# MCU.net
KiCad netlist of a schematic drawn in Altium Designer
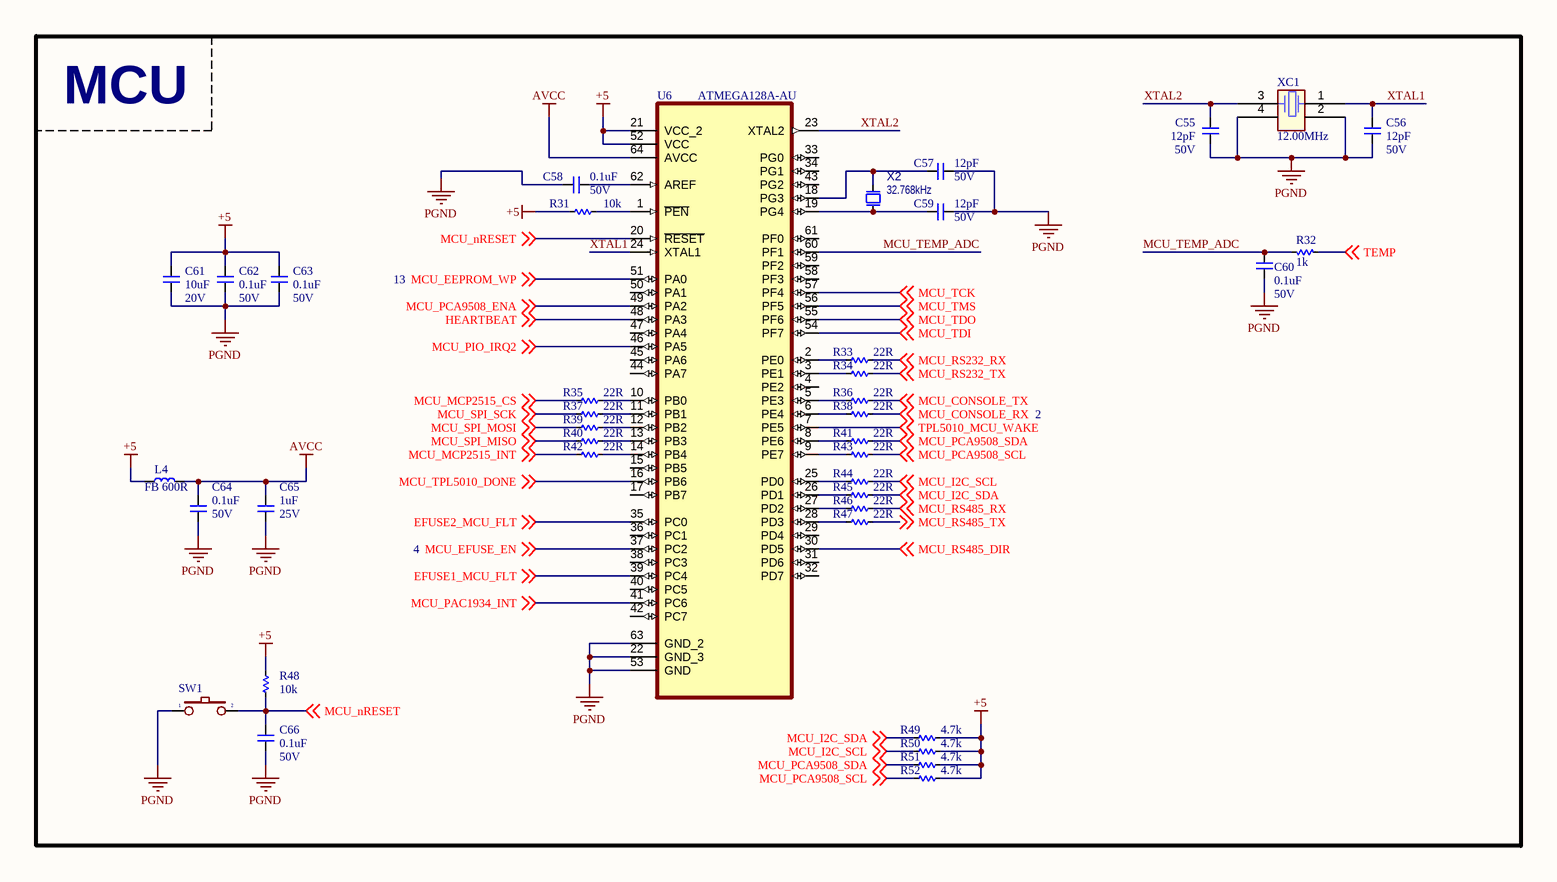
[diagram p0: MCU.SchDoc, left]
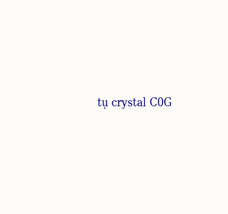
[diagram p1: MCU.SchDoc, right]

(export (version "E")
  (design (tool "Eeschema 10.0.6"))
  (components
    (comp (ref "C55")
      (value "12pF")
      (footprint "CAP_C_1608X80")
      (description "CAP")
      (fields (field (name "VOLTAGE") "50V"))
      (libsource (lib "LABLIB") (part "_CAP_C_2"))
    )
    (comp (ref "C56")
      (value "12pF")
      (footprint "CAP_C_1608X80")
      (description "CAP")
      (fields (field (name "VOLTAGE") "50V"))
      (libsource (lib "LABLIB") (part "_CAP_C_2"))
    )
    (comp (ref "C57")
      (value "12pF")
      (footprint "CAP_C_1608X80")
      (description "CAP")
      (fields (field (name "VOLTAGE") "50V"))
      (libsource (lib "LABLIB") (part "_CAP_C_2"))
    )
    (comp (ref "C58")
      (value "0.1uF")
      (footprint "CAP_C_1608X80")
      (description "CAP")
      (fields (field (name "VOLTAGE") "50V"))
      (libsource (lib "LABLIB") (part "_CAP_C_2"))
    )
    (comp (ref "C59")
      (value "12pF")
      (footprint "CAP_C_1608X80")
      (description "CAP")
      (fields (field (name "VOLTAGE") "50V"))
      (libsource (lib "LABLIB") (part "_CAP_C_2"))
    )
    (comp (ref "C60")
      (value "0.1uF")
      (footprint "CAP_C_1608X80")
      (description "CAP")
      (fields (field (name "VOLTAGE") "50V"))
      (libsource (lib "LABLIB") (part "_CAP_C_2"))
    )
    (comp (ref "C61")
      (value "10uF")
      (footprint "CAP_C_2012X110")
      (description "CAP")
      (fields (field (name "VOLTAGE") "20V"))
      (libsource (lib "LABLIB") (part "_CAP_C_2"))
    )
    (comp (ref "C62")
      (value "0.1uF")
      (footprint "CAP_C_1608X80")
      (description "CAP")
      (fields (field (name "VOLTAGE") "50V"))
      (libsource (lib "LABLIB") (part "_CAP_C_2"))
    )
    (comp (ref "C63")
      (value "0.1uF")
      (footprint "CAP_C_1608X80")
      (description "CAP")
      (fields (field (name "VOLTAGE") "50V"))
      (libsource (lib "LABLIB") (part "_CAP_C_2"))
    )
    (comp (ref "C64")
      (value "0.1uF")
      (footprint "CAP_C_1608X80")
      (description "CAP")
      (fields (field (name "VOLTAGE") "50V"))
      (libsource (lib "LABLIB") (part "_CAP_C_2"))
    )
    (comp (ref "C65")
      (value "1uF")
      (footprint "CAP_C_1608X80")
      (description "CAP")
      (fields (field (name "VOLTAGE") "25V"))
      (libsource (lib "LABLIB") (part "_CAP_C_2"))
    )
    (comp (ref "C66")
      (value "0.1uF")
      (footprint "CAP_C_1608X80")
      (description "CAP")
      (fields (field (name "VOLTAGE") "50V"))
      (libsource (lib "LABLIB") (part "_CAP_C_2"))
    )
    (comp (ref "L4")
      (value "FB 600R")
      (footprint "L-SMD-0603")
      (description "Ferrite Bread")
      (libsource (lib "chipfc_libs") (part "Inductor"))
    )
    (comp (ref "R31")
      (value "10k")
      (footprint "RES_C_1608X60")
      (description "RES")
      (libsource (lib "LABLIB") (part "_RES_B_2_2"))
    )
    (comp (ref "R32")
      (value "1k")
      (footprint "RES_C_1608X60")
      (description "RES")
      (libsource (lib "LABLIB") (part "_RES_B_2_2"))
    )
    (comp (ref "R33")
      (value "22R")
      (footprint "RES_C_1608X60")
      (description "RES")
      (libsource (lib "LABLIB") (part "_RES_B_2_2"))
    )
    (comp (ref "R34")
      (value "22R")
      (footprint "RES_C_1608X60")
      (description "RES")
      (libsource (lib "LABLIB") (part "_RES_B_2_2"))
    )
    (comp (ref "R35")
      (value "22R")
      (footprint "RES_C_1608X60")
      (description "RES")
      (libsource (lib "LABLIB") (part "_RES_B_2_2"))
    )
    (comp (ref "R36")
      (value "22R")
      (footprint "RES_C_1608X60")
      (description "RES")
      (libsource (lib "LABLIB") (part "_RES_B_2_2"))
    )
    (comp (ref "R37")
      (value "22R")
      (footprint "RES_C_1608X60")
      (description "RES")
      (libsource (lib "LABLIB") (part "_RES_B_2_2"))
    )
    (comp (ref "R38")
      (value "22R")
      (footprint "RES_C_1608X60")
      (description "RES")
      (libsource (lib "LABLIB") (part "_RES_B_2_2"))
    )
    (comp (ref "R39")
      (value "22R")
      (footprint "RES_C_1608X60")
      (description "RES")
      (libsource (lib "LABLIB") (part "_RES_B_2_2"))
    )
    (comp (ref "R40")
      (value "22R")
      (footprint "RES_C_1608X60")
      (description "RES")
      (libsource (lib "LABLIB") (part "_RES_B_2_2"))
    )
    (comp (ref "R41")
      (value "22R")
      (footprint "RES_C_1608X60")
      (description "RES")
      (libsource (lib "LABLIB") (part "_RES_B_2_2"))
    )
    (comp (ref "R42")
      (value "22R")
      (footprint "RES_C_1608X60")
      (description "RES")
      (libsource (lib "LABLIB") (part "_RES_B_2_2"))
    )
    (comp (ref "R43")
      (value "22R")
      (footprint "RES_C_1608X60")
      (description "RES")
      (libsource (lib "LABLIB") (part "_RES_B_2_2"))
    )
    (comp (ref "R44")
      (value "22R")
      (footprint "RES_C_1608X60")
      (description "RES")
      (libsource (lib "LABLIB") (part "_RES_B_2_2"))
    )
    (comp (ref "R45")
      (value "22R")
      (footprint "RES_C_1608X60")
      (description "RES")
      (libsource (lib "LABLIB") (part "_RES_B_2_2"))
    )
    (comp (ref "R46")
      (value "22R")
      (footprint "RES_C_1608X60")
      (description "RES")
      (libsource (lib "LABLIB") (part "_RES_B_2_2"))
    )
    (comp (ref "R47")
      (value "22R")
      (footprint "RES_C_1608X60")
      (description "RES")
      (libsource (lib "LABLIB") (part "_RES_B_2_2"))
    )
    (comp (ref "R48")
      (value "10k")
      (footprint "RES_C_1608X60")
      (description "RES")
      (libsource (lib "LABLIB") (part "_RES_B_2_2"))
    )
    (comp (ref "R49")
      (value "4.7k")
      (footprint "RES_C_1608X60")
      (description "RES")
      (libsource (lib "LABLIB") (part "_RES_B_2_2"))
    )
    (comp (ref "R50")
      (value "4.7k")
      (footprint "RES_C_1608X60")
      (description "RES")
      (libsource (lib "LABLIB") (part "_RES_B_2_2"))
    )
    (comp (ref "R51")
      (value "4.7k")
      (footprint "RES_C_1608X60")
      (description "RES")
      (libsource (lib "LABLIB") (part "_RES_B_2_2"))
    )
    (comp (ref "R52")
      (value "4.7k")
      (footprint "RES_C_1608X60")
      (description "RES")
      (libsource (lib "LABLIB") (part "_RES_B_2_2"))
    )
    (comp (ref "SW1")
      (value "SW2")
      (footprint "SW1-SMD")
      (description "Switch button 2 pin")
      (libsource (lib "LABLIB") (part "SW2"))
    )
    (comp (ref "U6")
      (value "ATMEGA128A-AU")
      (footprint "TQFP-64")
      (libsource (lib "KIENASIY123_LIB") (part "ATMEGA128A-AU"))
    )
    (comp (ref "X2")
      (value "32.768kHz")
      (footprint "CRYSTAL_NX2012SA")
      (description "Crystal")
      (fields
        (field (name "TOLERANCE") "±20ppm")
        (field (name "Comment") "Crystal 2 Pins")
        (field (name "OWNER") "Jamus Griego")
      )
      (libsource (lib "LABLIB") (part "OSC_32.768kHz"))
    )
    (comp (ref "XC1")
      (value "12.00MHz")
      (footprint "AP7-00039")
      (description "Fox FQ5032B 12.0MHz SMD crystal 738B-12")
      (fields (field (name "TOLERANCE") "Â±30ppm") (field (name "MANUFACTURER") "Fox  Electronics"))
      (libsource (lib "AltiumDbLib") (part "CRYSTAL1324"))
    )
  )
  (nets
    (net (code "1") (name "+5") (class "Default")
      (node (ref "C61") (pin "2") (pinfunction "2_2") (pintype "passive"))
      (node (ref "C62") (pin "1") (pinfunction "1_1") (pintype "passive"))
      (node (ref "C63") (pin "1") (pinfunction "1_1") (pintype "passive"))
      (node (ref "L4") (pin "1") (pinfunction "1_1") (pintype "passive"))
      (node (ref "R31") (pin "1") (pinfunction "1_1") (pintype "passive"))
      (node (ref "R48") (pin "1") (pinfunction "1_1") (pintype "passive"))
      (node (ref "R49") (pin "1") (pinfunction "1_1") (pintype "passive"))
      (node (ref "R50") (pin "1") (pinfunction "1_1") (pintype "passive"))
      (node (ref "R51") (pin "1") (pinfunction "1_1") (pintype "passive"))
      (node (ref "R52") (pin "1") (pinfunction "1_1") (pintype "passive"))
      (node (ref "U6") (pin "21") (pinfunction "VCC_2_21") (pintype "power_in"))
      (node (ref "U6") (pin "52") (pinfunction "VCC_52") (pintype "power_in"))
    )
    (net (code "2") (name "/MCU_TEMP_ADC") (class "Default")
      (node (ref "C60") (pin "1") (pinfunction "1_1") (pintype "passive"))
      (node (ref "R32") (pin "2") (pinfunction "2_2") (pintype "passive"))
      (node (ref "U6") (pin "60") (pinfunction "PF1_60") (pintype "bidirectional"))
    )
    (net (code "3") (name "/XTAL1") (class "Default")
      (node (ref "C56") (pin "2") (pinfunction "2_2") (pintype "passive"))
      (node (ref "U6") (pin "24") (pinfunction "XTAL1_24") (pintype "input"))
      (node (ref "XC1") (pin "1") (pinfunction "1_1") (pintype "passive"))
    )
    (net (code "4") (name "/XTAL2") (class "Default")
      (node (ref "C55") (pin "2") (pinfunction "2_2") (pintype "passive"))
      (node (ref "U6") (pin "23") (pinfunction "XTAL2_23") (pintype "output"))
      (node (ref "XC1") (pin "3") (pinfunction "3_3") (pintype "passive"))
    )
    (net (code "5") (name "AVCC") (class "Default")
      (node (ref "C64") (pin "1") (pinfunction "1_1") (pintype "passive"))
      (node (ref "C65") (pin "1") (pinfunction "1_1") (pintype "passive"))
      (node (ref "L4") (pin "2") (pinfunction "2_2") (pintype "passive"))
      (node (ref "U6") (pin "64") (pinfunction "AVCC_64") (pintype "power_in"))
    )
    (net (code "6") (name "EFUSE1_MCU_FLT") (class "Default")
      (node (ref "U6") (pin "39") (pinfunction "PC4_39") (pintype "bidirectional"))
    )
    (net (code "7") (name "EFUSE2_MCU_FLT") (class "Default")
      (node (ref "U6") (pin "35") (pinfunction "PC0_35") (pintype "bidirectional"))
    )
    (net (code "8") (name "HEARTBEAT") (class "Default")
      (node (ref "U6") (pin "48") (pinfunction "PA3_48") (pintype "bidirectional"))
    )
    (net (code "9") (name "MCU_CONSOLE_RX") (class "Default")
      (node (ref "R38") (pin "2") (pinfunction "2_2") (pintype "passive"))
    )
    (net (code "10") (name "MCU_CONSOLE_TX") (class "Default")
      (node (ref "R36") (pin "2") (pinfunction "2_2") (pintype "passive"))
    )
    (net (code "11") (name "MCU_EEPROM_WP") (class "Default")
      (node (ref "U6") (pin "51") (pinfunction "PA0_51") (pintype "bidirectional"))
    )
    (net (code "12") (name "MCU_EFUSE_EN") (class "Default")
      (node (ref "U6") (pin "37") (pinfunction "PC2_37") (pintype "bidirectional"))
    )
    (net (code "13") (name "MCU_I2C_SCL") (class "Default")
      (node (ref "R44") (pin "2") (pinfunction "2_2") (pintype "passive"))
      (node (ref "R50") (pin "2") (pinfunction "2_2") (pintype "passive"))
    )
    (net (code "14") (name "MCU_I2C_SDA") (class "Default")
      (node (ref "R45") (pin "2") (pinfunction "2_2") (pintype "passive"))
      (node (ref "R49") (pin "2") (pinfunction "2_2") (pintype "passive"))
    )
    (net (code "15") (name "MCU_MCP2515_CS") (class "Default")
      (node (ref "R35") (pin "1") (pinfunction "1_1") (pintype "passive"))
    )
    (net (code "16") (name "MCU_MCP2515_INT") (class "Default")
      (node (ref "R42") (pin "1") (pinfunction "1_1") (pintype "passive"))
    )
    (net (code "17") (name "MCU_PAC1934_INT") (class "Default")
      (node (ref "U6") (pin "41") (pinfunction "PC6_41") (pintype "bidirectional"))
    )
    (net (code "18") (name "MCU_PCA9508_ENA") (class "Default")
      (node (ref "U6") (pin "49") (pinfunction "PA2_49") (pintype "bidirectional"))
    )
    (net (code "19") (name "MCU_PCA9508_SCL") (class "Default")
      (node (ref "R43") (pin "2") (pinfunction "2_2") (pintype "passive"))
      (node (ref "R52") (pin "2") (pinfunction "2_2") (pintype "passive"))
    )
    (net (code "20") (name "MCU_PCA9508_SDA") (class "Default")
      (node (ref "R41") (pin "2") (pinfunction "2_2") (pintype "passive"))
      (node (ref "R51") (pin "2") (pinfunction "2_2") (pintype "passive"))
    )
    (net (code "21") (name "MCU_PIO_IRQ2") (class "Default")
      (node (ref "U6") (pin "46") (pinfunction "PA5_46") (pintype "bidirectional"))
    )
    (net (code "22") (name "MCU_RS232_RX") (class "Default")
      (node (ref "R33") (pin "2") (pinfunction "2_2") (pintype "passive"))
    )
    (net (code "23") (name "MCU_RS232_TX") (class "Default")
      (node (ref "R34") (pin "2") (pinfunction "2_2") (pintype "passive"))
    )
    (net (code "24") (name "MCU_RS485_DIR") (class "Default")
      (node (ref "U6") (pin "30") (pinfunction "PD5_30") (pintype "bidirectional"))
    )
    (net (code "25") (name "MCU_RS485_RX") (class "Default")
      (node (ref "R46") (pin "2") (pinfunction "2_2") (pintype "passive"))
    )
    (net (code "26") (name "MCU_RS485_TX") (class "Default")
      (node (ref "R47") (pin "2") (pinfunction "2_2") (pintype "passive"))
    )
    (net (code "27") (name "MCU_SPI_MISO") (class "Default")
      (node (ref "R40") (pin "1") (pinfunction "1_1") (pintype "passive"))
    )
    (net (code "28") (name "MCU_SPI_MOSI") (class "Default")
      (node (ref "R39") (pin "1") (pinfunction "1_1") (pintype "passive"))
    )
    (net (code "29") (name "MCU_SPI_SCK") (class "Default")
      (node (ref "R37") (pin "1") (pinfunction "1_1") (pintype "passive"))
    )
    (net (code "30") (name "MCU_TCK") (class "Default")
      (node (ref "U6") (pin "57") (pinfunction "PF4_57") (pintype "bidirectional"))
    )
    (net (code "31") (name "MCU_TDI") (class "Default")
      (node (ref "U6") (pin "54") (pinfunction "PF7_54") (pintype "bidirectional"))
    )
    (net (code "32") (name "MCU_TDO") (class "Default")
      (node (ref "U6") (pin "55") (pinfunction "PF6_55") (pintype "bidirectional"))
    )
    (net (code "33") (name "MCU_TMS") (class "Default")
      (node (ref "U6") (pin "56") (pinfunction "PF5_56") (pintype "bidirectional"))
    )
    (net (code "34") (name "MCU_TPL5010_DONE") (class "Default")
      (node (ref "U6") (pin "16") (pinfunction "PB6_16") (pintype "bidirectional"))
    )
    (net (code "35") (name "MCU_nRESET") (class "Default")
      (node (ref "C66") (pin "2") (pinfunction "2_2") (pintype "passive"))
      (node (ref "R48") (pin "2") (pinfunction "2_2") (pintype "passive"))
      (node (ref "SW1") (pin "2") (pinfunction "2_2") (pintype "passive"))
      (node (ref "U6") (pin "20") (pinfunction "~{RESET}_20") (pintype "input"))
    )
    (net (code "36") (name "Net-(U6-AREF)") (class "Default")
      (node (ref "C58") (pin "1") (pinfunction "1_1") (pintype "passive"))
      (node (ref "U6") (pin "62") (pinfunction "AREF_62") (pintype "input"))
    )
    (net (code "37") (name "Net-(U6-PB0)") (class "Default")
      (node (ref "R35") (pin "2") (pinfunction "2_2") (pintype "passive"))
      (node (ref "U6") (pin "10") (pinfunction "PB0_10") (pintype "bidirectional"))
    )
    (net (code "38") (name "Net-(U6-PB1)") (class "Default")
      (node (ref "R37") (pin "2") (pinfunction "2_2") (pintype "passive"))
      (node (ref "U6") (pin "11") (pinfunction "PB1_11") (pintype "bidirectional"))
    )
    (net (code "39") (name "Net-(U6-PB2)") (class "Default")
      (node (ref "R39") (pin "2") (pinfunction "2_2") (pintype "passive"))
      (node (ref "U6") (pin "12") (pinfunction "PB2_12") (pintype "bidirectional"))
    )
    (net (code "40") (name "Net-(U6-PB3)") (class "Default")
      (node (ref "R40") (pin "2") (pinfunction "2_2") (pintype "passive"))
      (node (ref "U6") (pin "13") (pinfunction "PB3_13") (pintype "bidirectional"))
    )
    (net (code "41") (name "Net-(U6-PB4)") (class "Default")
      (node (ref "R42") (pin "2") (pinfunction "2_2") (pintype "passive"))
      (node (ref "U6") (pin "14") (pinfunction "PB4_14") (pintype "bidirectional"))
    )
    (net (code "42") (name "Net-(U6-PD0)") (class "Default")
      (node (ref "R44") (pin "1") (pinfunction "1_1") (pintype "passive"))
      (node (ref "U6") (pin "25") (pinfunction "PD0_25") (pintype "bidirectional"))
    )
    (net (code "43") (name "Net-(U6-PD1)") (class "Default")
      (node (ref "R45") (pin "1") (pinfunction "1_1") (pintype "passive"))
      (node (ref "U6") (pin "26") (pinfunction "PD1_26") (pintype "bidirectional"))
    )
    (net (code "44") (name "Net-(U6-PD2)") (class "Default")
      (node (ref "R46") (pin "1") (pinfunction "1_1") (pintype "passive"))
      (node (ref "U6") (pin "27") (pinfunction "PD2_27") (pintype "bidirectional"))
    )
    (net (code "45") (name "Net-(U6-PD3)") (class "Default")
      (node (ref "R47") (pin "1") (pinfunction "1_1") (pintype "passive"))
      (node (ref "U6") (pin "28") (pinfunction "PD3_28") (pintype "bidirectional"))
    )
    (net (code "46") (name "Net-(U6-PE0)") (class "Default")
      (node (ref "R33") (pin "1") (pinfunction "1_1") (pintype "passive"))
      (node (ref "U6") (pin "2") (pinfunction "PE0_2") (pintype "bidirectional"))
    )
    (net (code "47") (name "Net-(U6-PE1)") (class "Default")
      (node (ref "R34") (pin "1") (pinfunction "1_1") (pintype "passive"))
      (node (ref "U6") (pin "3") (pinfunction "PE1_3") (pintype "bidirectional"))
    )
    (net (code "48") (name "Net-(U6-PE3)") (class "Default")
      (node (ref "R36") (pin "1") (pinfunction "1_1") (pintype "passive"))
      (node (ref "U6") (pin "5") (pinfunction "PE3_5") (pintype "bidirectional"))
    )
    (net (code "49") (name "Net-(U6-PE4)") (class "Default")
      (node (ref "R38") (pin "1") (pinfunction "1_1") (pintype "passive"))
      (node (ref "U6") (pin "6") (pinfunction "PE4_6") (pintype "bidirectional"))
    )
    (net (code "50") (name "Net-(U6-PE6)") (class "Default")
      (node (ref "R41") (pin "1") (pinfunction "1_1") (pintype "passive"))
      (node (ref "U6") (pin "8") (pinfunction "PE6_8") (pintype "bidirectional"))
    )
    (net (code "51") (name "Net-(U6-PE7)") (class "Default")
      (node (ref "R43") (pin "1") (pinfunction "1_1") (pintype "passive"))
      (node (ref "U6") (pin "9") (pinfunction "PE7_9") (pintype "bidirectional"))
    )
    (net (code "52") (name "Net-(U6-PG3)") (class "Default")
      (node (ref "C57") (pin "2") (pinfunction "2_2") (pintype "passive"))
      (node (ref "U6") (pin "18") (pinfunction "PG3_18") (pintype "bidirectional"))
      (node (ref "X2") (pin "2") (pinfunction "Osc2_2") (pintype "passive"))
    )
    (net (code "53") (name "Net-(U6-PG4)") (class "Default")
      (node (ref "C59") (pin "2") (pinfunction "2_2") (pintype "passive"))
      (node (ref "U6") (pin "19") (pinfunction "PG4_19") (pintype "bidirectional"))
      (node (ref "X2") (pin "1") (pinfunction "Osc1_1") (pintype "passive"))
    )
    (net (code "54") (name "Net-(U6-~{PEN})") (class "Default")
      (node (ref "R31") (pin "2") (pinfunction "2_2") (pintype "passive"))
      (node (ref "U6") (pin "1") (pinfunction "~{PEN}_1") (pintype "input"))
    )
    (net (code "55") (name "PGND") (class "Default")
      (node (ref "C55") (pin "1") (pinfunction "1_1") (pintype "passive"))
      (node (ref "C56") (pin "1") (pinfunction "1_1") (pintype "passive"))
      (node (ref "C57") (pin "1") (pinfunction "1_1") (pintype "passive"))
      (node (ref "C58") (pin "2") (pinfunction "2_2") (pintype "passive"))
      (node (ref "C59") (pin "1") (pinfunction "1_1") (pintype "passive"))
      (node (ref "C60") (pin "2") (pinfunction "2_2") (pintype "passive"))
      (node (ref "C61") (pin "1") (pinfunction "1_1") (pintype "passive"))
      (node (ref "C62") (pin "2") (pinfunction "2_2") (pintype "passive"))
      (node (ref "C63") (pin "2") (pinfunction "2_2") (pintype "passive"))
      (node (ref "C64") (pin "2") (pinfunction "2_2") (pintype "passive"))
      (node (ref "C65") (pin "2") (pinfunction "2_2") (pintype "passive"))
      (node (ref "C66") (pin "1") (pinfunction "1_1") (pintype "passive"))
      (node (ref "SW1") (pin "1") (pinfunction "1_1") (pintype "passive"))
      (node (ref "U6") (pin "22") (pinfunction "GND_3_22") (pintype "passive"))
      (node (ref "U6") (pin "53") (pinfunction "GND_53") (pintype "passive"))
      (node (ref "U6") (pin "63") (pinfunction "GND_2_63") (pintype "passive"))
      (node (ref "XC1") (pin "2") (pinfunction "2_2") (pintype "passive"))
      (node (ref "XC1") (pin "4") (pinfunction "4_4") (pintype "passive"))
    )
    (net (code "56") (name "TEMP") (class "Default")
      (node (ref "R32") (pin "1") (pinfunction "1_1") (pintype "passive"))
    )
    (net (code "57") (name "TPL5010_MCU_WAKE") (class "Default")
      (node (ref "U6") (pin "7") (pinfunction "PE5_7") (pintype "bidirectional"))
    )
    (net (code "58") (name "unconnected-(U6-PA1-Pad50)") (class "Default")
      (node (ref "U6") (pin "50") (pinfunction "PA1_50") (pintype "bidirectional"))
    )
    (net (code "59") (name "unconnected-(U6-PA4-Pad47)") (class "Default")
      (node (ref "U6") (pin "47") (pinfunction "PA4_47") (pintype "bidirectional"))
    )
    (net (code "60") (name "unconnected-(U6-PA6-Pad45)") (class "Default")
      (node (ref "U6") (pin "45") (pinfunction "PA6_45") (pintype "bidirectional"))
    )
    (net (code "61") (name "unconnected-(U6-PA7-Pad44)") (class "Default")
      (node (ref "U6") (pin "44") (pinfunction "PA7_44") (pintype "bidirectional"))
    )
    (net (code "62") (name "unconnected-(U6-PB5-Pad15)") (class "Default")
      (node (ref "U6") (pin "15") (pinfunction "PB5_15") (pintype "bidirectional"))
    )
    (net (code "63") (name "unconnected-(U6-PB7-Pad17)") (class "Default")
      (node (ref "U6") (pin "17") (pinfunction "PB7_17") (pintype "bidirectional"))
    )
    (net (code "64") (name "unconnected-(U6-PC1-Pad36)") (class "Default")
      (node (ref "U6") (pin "36") (pinfunction "PC1_36") (pintype "bidirectional"))
    )
    (net (code "65") (name "unconnected-(U6-PC3-Pad38)") (class "Default")
      (node (ref "U6") (pin "38") (pinfunction "PC3_38") (pintype "bidirectional"))
    )
    (net (code "66") (name "unconnected-(U6-PC5-Pad40)") (class "Default")
      (node (ref "U6") (pin "40") (pinfunction "PC5_40") (pintype "bidirectional"))
    )
    (net (code "67") (name "unconnected-(U6-PC7-Pad42)") (class "Default")
      (node (ref "U6") (pin "42") (pinfunction "PC7_42") (pintype "bidirectional"))
    )
    (net (code "68") (name "unconnected-(U6-PD4-Pad29)") (class "Default")
      (node (ref "U6") (pin "29") (pinfunction "PD4_29") (pintype "bidirectional"))
    )
    (net (code "69") (name "unconnected-(U6-PD6-Pad31)") (class "Default")
      (node (ref "U6") (pin "31") (pinfunction "PD6_31") (pintype "bidirectional"))
    )
    (net (code "70") (name "unconnected-(U6-PD7-Pad32)") (class "Default")
      (node (ref "U6") (pin "32") (pinfunction "PD7_32") (pintype "bidirectional"))
    )
    (net (code "71") (name "unconnected-(U6-PE2-Pad4)") (class "Default")
      (node (ref "U6") (pin "4") (pinfunction "PE2_4") (pintype "bidirectional"))
    )
    (net (code "72") (name "unconnected-(U6-PF0-Pad61)") (class "Default")
      (node (ref "U6") (pin "61") (pinfunction "PF0_61") (pintype "bidirectional"))
    )
    (net (code "73") (name "unconnected-(U6-PF2-Pad59)") (class "Default")
      (node (ref "U6") (pin "59") (pinfunction "PF2_59") (pintype "bidirectional"))
    )
    (net (code "74") (name "unconnected-(U6-PF3-Pad58)") (class "Default")
      (node (ref "U6") (pin "58") (pinfunction "PF3_58") (pintype "bidirectional"))
    )
    (net (code "75") (name "unconnected-(U6-PG0-Pad33)") (class "Default")
      (node (ref "U6") (pin "33") (pinfunction "PG0_33") (pintype "bidirectional"))
    )
    (net (code "76") (name "unconnected-(U6-PG1-Pad34)") (class "Default")
      (node (ref "U6") (pin "34") (pinfunction "PG1_34") (pintype "bidirectional"))
    )
    (net (code "77") (name "unconnected-(U6-PG2-Pad43)") (class "Default")
      (node (ref "U6") (pin "43") (pinfunction "PG2_43") (pintype "bidirectional"))
    )
  )
)
